# 12_CONSOLE.net
KiCad netlist of a schematic drawn in Altium Designer
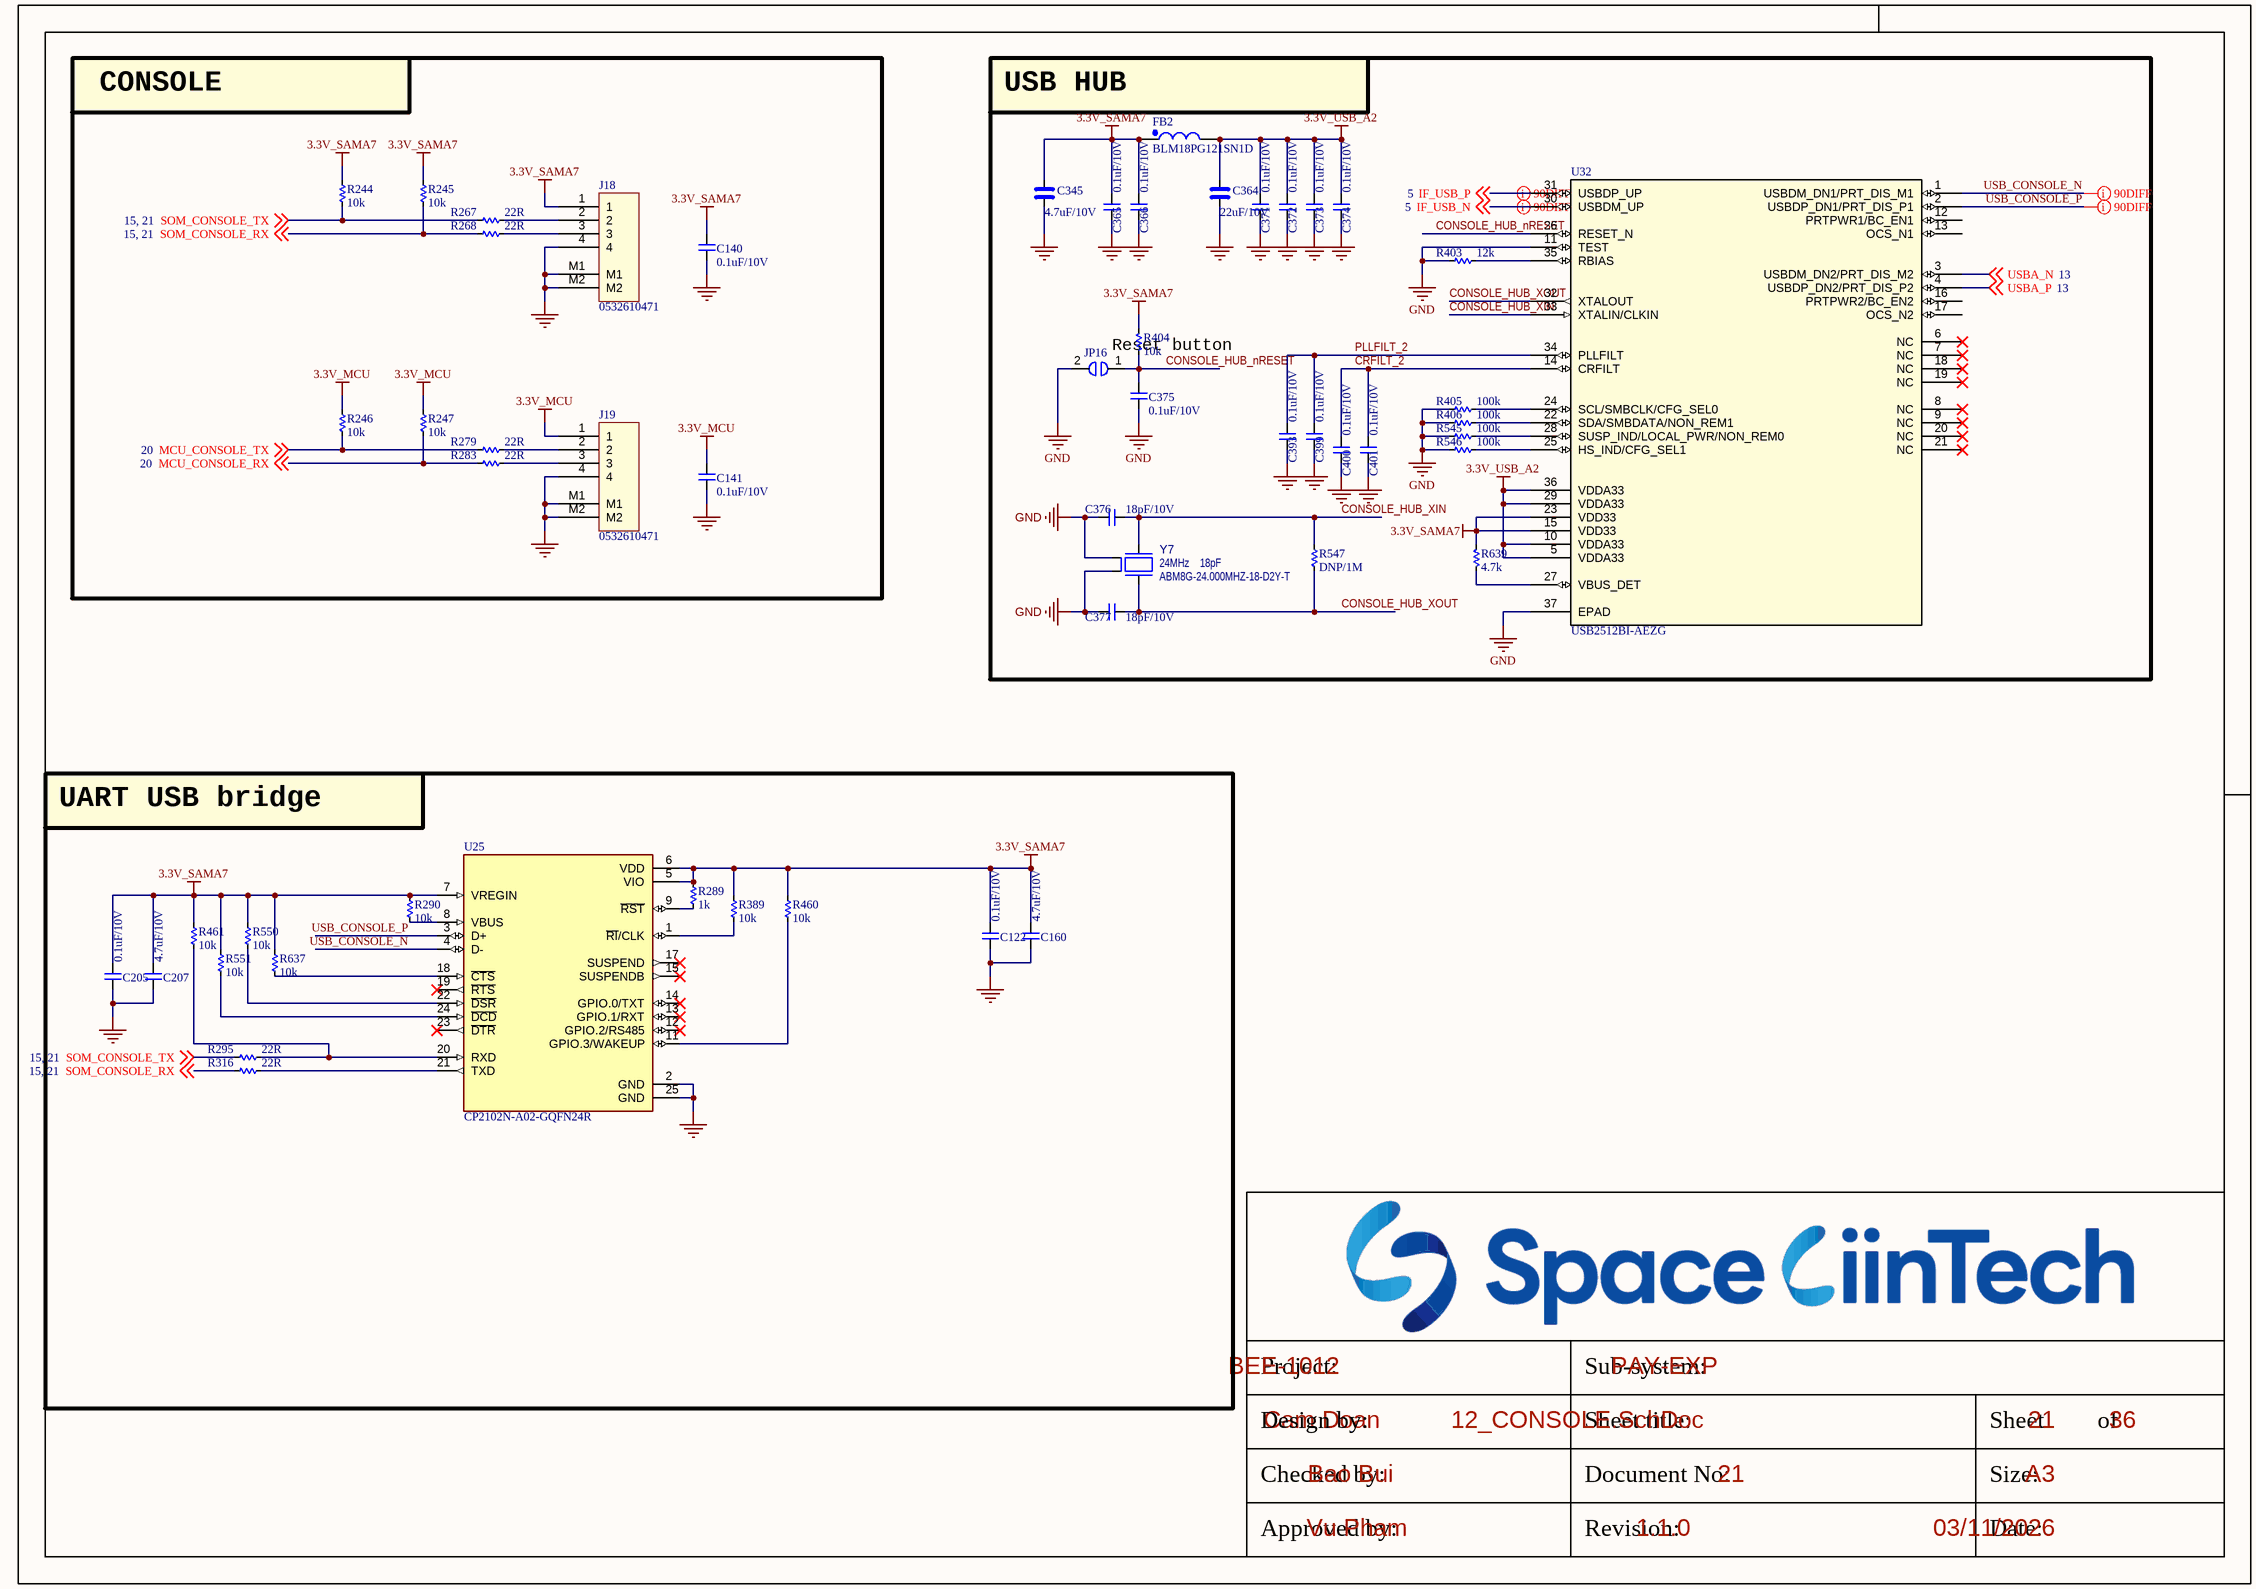
[diagram p0: 12_CONSOLE.SchDoc]

(export (version "E")
  (design (tool "Eeschema 10.0.6"))
  (components
    (comp (ref "C122")
      (value "0.1uF/10V")
      (footprint "CAP_C_1005X60")
      (description "CAP")
      (libsource (lib "LABLIB") (part "_CAP_C_2"))
    )
    (comp (ref "C140")
      (value "0.1uF/10V")
      (footprint "CAP_C_1005X60")
      (description "CAP")
      (libsource (lib "LABLIB") (part "_CAP_C_2"))
    )
    (comp (ref "C141")
      (value "0.1uF/10V")
      (footprint "CAP_C_1005X60")
      (description "CAP")
      (libsource (lib "LABLIB") (part "_CAP_C_2"))
    )
    (comp (ref "C160")
      (value "4.7uF/10V")
      (footprint "CAP_C_1005X60")
      (description "CAP")
      (libsource (lib "LABLIB") (part "_CAP_C_2"))
    )
    (comp (ref "C205")
      (value "0.1uF/10V")
      (footprint "CAP_C_1005X60")
      (description "CAP")
      (libsource (lib "LABLIB") (part "_CAP_C_2"))
    )
    (comp (ref "C207")
      (value "4.7uF/10V")
      (footprint "CAP_C_1005X60")
      (description "CAP")
      (libsource (lib "LABLIB") (part "_CAP_C_2"))
    )
    (comp (ref "C345")
      (value "4.7uF/10V")
      (footprint "CAP_C_1608X80")
      (description "CAP CHIP High Value")
      (libsource (lib "LABLIB") (part "_CAP_C_High_2"))
    )
    (comp (ref "C364")
      (value "22uF/10V")
      (footprint "CAP_C_1608X80")
      (description "CAP CHIP High Value")
      (libsource (lib "LABLIB") (part "_CAP_C_High_2"))
    )
    (comp (ref "C365")
      (value "0.1uF/10V")
      (footprint "CAP_C_1005X60")
      (description "CAP CHIP")
      (libsource (lib "LABLIB") (part "_CAP_C_2"))
    )
    (comp (ref "C366")
      (value "0.1uF/10V")
      (footprint "CAP_C_1005X60")
      (description "CAP CHIP")
      (libsource (lib "LABLIB") (part "_CAP_C_2"))
    )
    (comp (ref "C371")
      (value "0.1uF/10V")
      (footprint "CAP_C_1005X60")
      (description "CAP CHIP")
      (libsource (lib "LABLIB") (part "_CAP_C_2"))
    )
    (comp (ref "C372")
      (value "0.1uF/10V")
      (footprint "CAP_C_1005X60")
      (description "CAP CHIP")
      (libsource (lib "LABLIB") (part "_CAP_C_2"))
    )
    (comp (ref "C373")
      (value "0.1uF/10V")
      (footprint "CAP_C_1005X60")
      (description "CAP CHIP")
      (libsource (lib "LABLIB") (part "_CAP_C_2"))
    )
    (comp (ref "C374")
      (value "0.1uF/10V")
      (footprint "CAP_C_1005X60")
      (description "CAP CHIP")
      (libsource (lib "LABLIB") (part "_CAP_C_2"))
    )
    (comp (ref "C375")
      (value "0.1uF/10V")
      (footprint "CAP_C_1005X60")
      (description "CAP CHIP")
      (libsource (lib "LABLIB") (part "_CAP_C_2"))
    )
    (comp (ref "C376")
      (value "18pF/10V")
      (footprint "CAP_C_1005X60")
      (description "CAP CHIP")
      (libsource (lib "LABLIB") (part "_CAP_C_2"))
    )
    (comp (ref "C377")
      (value "18pF/10V")
      (footprint "CAP_C_1005X60")
      (description "CAP CHIP")
      (libsource (lib "LABLIB") (part "_CAP_C_2"))
    )
    (comp (ref "C393")
      (value "0.1uF/10V")
      (footprint "CAP_C_1005X60")
      (description "CAP CHIP")
      (libsource (lib "LABLIB") (part "_CAP_C_2"))
    )
    (comp (ref "C399")
      (value "0.1uF/10V")
      (footprint "CAP_C_1005X60")
      (description "CAP CHIP")
      (libsource (lib "LABLIB") (part "_CAP_C_2"))
    )
    (comp (ref "C400")
      (value "0.1uF/10V")
      (footprint "CAP_C_1005X60")
      (description "CAP CHIP")
      (libsource (lib "LABLIB") (part "_CAP_C_2"))
    )
    (comp (ref "C401")
      (value "0.1uF/10V")
      (footprint "CAP_C_1005X60")
      (description "CAP CHIP")
      (libsource (lib "LABLIB") (part "_CAP_C_2"))
    )
    (comp (ref "FB2")
      (value "BLM18PG121SN1D")
      (footprint "IND_C_1608X60")
      (libsource (lib "LABLIB") (part "_IND"))
    )
    (comp (ref "J18")
      (value "0532610471")
      (footprint "MOLEX_0532610471")
      (libsource (lib "LABLIB") (part "Header 4x1_2M"))
    )
    (comp (ref "J19")
      (value "0532610471")
      (footprint "MOLEX_0532610471")
      (libsource (lib "LABLIB") (part "Header 4x1_2M"))
    )
    (comp (ref "JP16")
      (value "~")
      (footprint "TESTPOINT_SHORT_120X100_60")
      (libsource (lib "LABLIB") (part "JUMPER_1_1"))
    )
    (comp (ref "R244")
      (value "10k")
      (footprint "RES_C_1005X40")
      (description "RES")
      (libsource (lib "LABLIB") (part "_RES_B_2"))
    )
    (comp (ref "R245")
      (value "10k")
      (footprint "RES_C_1005X40")
      (description "RES")
      (libsource (lib "LABLIB") (part "_RES_B_2"))
    )
    (comp (ref "R246")
      (value "10k")
      (footprint "RES_C_1005X40")
      (description "RES")
      (libsource (lib "LABLIB") (part "_RES_B_2"))
    )
    (comp (ref "R247")
      (value "10k")
      (footprint "RES_C_1005X40")
      (description "RES")
      (libsource (lib "LABLIB") (part "_RES_B_2"))
    )
    (comp (ref "R267")
      (value "22R")
      (footprint "RES_C_1005X40")
      (description "RES")
      (libsource (lib "LABLIB") (part "_RES_B_2"))
    )
    (comp (ref "R268")
      (value "22R")
      (footprint "RES_C_1005X40")
      (description "RES")
      (libsource (lib "LABLIB") (part "_RES_B_2"))
    )
    (comp (ref "R279")
      (value "22R")
      (footprint "RES_C_1005X40")
      (description "RES")
      (libsource (lib "LABLIB") (part "_RES_B_2"))
    )
    (comp (ref "R283")
      (value "22R")
      (footprint "RES_C_1005X40")
      (description "RES")
      (libsource (lib "LABLIB") (part "_RES_B_2"))
    )
    (comp (ref "R289")
      (value "1k")
      (footprint "RES_C_1005X40")
      (description "RES")
      (libsource (lib "LABLIB") (part "_RES_B_2"))
    )
    (comp (ref "R290")
      (value "10k")
      (footprint "RES_C_1005X40")
      (description "RES")
      (libsource (lib "LABLIB") (part "_RES_B_2"))
    )
    (comp (ref "R295")
      (value "22R")
      (footprint "RES_C_1005X40")
      (description "RES")
      (libsource (lib "LABLIB") (part "_RES_B_2"))
    )
    (comp (ref "R316")
      (value "22R")
      (footprint "RES_C_1005X40")
      (description "RES")
      (libsource (lib "LABLIB") (part "_RES_B_2"))
    )
    (comp (ref "R389")
      (value "10k")
      (footprint "RES_C_1005X40")
      (description "RES")
      (libsource (lib "LABLIB") (part "_RES_B_2"))
    )
    (comp (ref "R403")
      (value "12k")
      (footprint "RES_C_1005X40")
      (description "RES")
      (libsource (lib "LABLIB") (part "_RES_B_2"))
    )
    (comp (ref "R404")
      (value "10k")
      (footprint "RES_C_1005X40")
      (description "RES")
      (libsource (lib "LABLIB") (part "_RES_B_2"))
    )
    (comp (ref "R405")
      (value "100k")
      (footprint "RES_C_1005X40")
      (description "RES")
      (libsource (lib "LABLIB") (part "_RES_B_2"))
    )
    (comp (ref "R406")
      (value "100k")
      (footprint "RES_C_1005X40")
      (description "RES")
      (libsource (lib "LABLIB") (part "_RES_B_2"))
    )
    (comp (ref "R460")
      (value "10k")
      (footprint "RES_C_1005X40")
      (description "RES")
      (libsource (lib "LABLIB") (part "_RES_B_2"))
    )
    (comp (ref "R461")
      (value "10k")
      (footprint "RES_C_1005X40")
      (description "RES")
      (libsource (lib "LABLIB") (part "_RES_B_2"))
    )
    (comp (ref "R545")
      (value "100k")
      (footprint "RES_C_1005X40")
      (description "RES")
      (libsource (lib "LABLIB") (part "_RES_B_2"))
    )
    (comp (ref "R546")
      (value "100k")
      (footprint "RES_C_1005X40")
      (description "RES")
      (libsource (lib "LABLIB") (part "_RES_B_2"))
    )
    (comp (ref "R547")
      (value "DNP/1M")
      (footprint "RES_C_1005X40")
      (description "RES")
      (libsource (lib "LABLIB") (part "_RES_B_2"))
    )
    (comp (ref "R550")
      (value "10k")
      (footprint "RES_C_1005X40")
      (description "RES")
      (libsource (lib "LABLIB") (part "_RES_B_2"))
    )
    (comp (ref "R551")
      (value "10k")
      (footprint "RES_C_1005X40")
      (description "RES")
      (libsource (lib "LABLIB") (part "_RES_B_2"))
    )
    (comp (ref "R637")
      (value "10k")
      (footprint "RES_C_1005X40")
      (description "RES")
      (libsource (lib "LABLIB") (part "_RES_B_2"))
    )
    (comp (ref "R639")
      (value "4.7k")
      (footprint "RES_C_1005X40")
      (description "RES")
      (libsource (lib "LABLIB") (part "_RES_B_2"))
    )
    (comp (ref "U25")
      (value "CP2102N-A02-GQFN24R")
      (footprint "QFN50P400X400X80-25N")
      (libsource (lib "LABLIB") (part "IC_USB_toUART_CP2102N-A02-GQFN24R"))
    )
    (comp (ref "U32")
      (value "USB2512BI-AEZG")
      (footprint "QFN36_6X6MC_MCH")
      (description "Description")
      (fields (field (name "COPYRIGHT") "Copyright (C) 2026 Ultra Librarian. All rights reserved."))
      (libsource (lib "LABLIB") (part "IC_USB_HUB_USB2512BI-AEZG"))
    )
    (comp (ref "Y7")
      (value "24MHz")
      (footprint "CRYSTAL_ABM8G")
      (description "Crystal")
      (fields
        (field (name "LOAD CAPACITANCE") "18pF")
        (field (name "MANUFACTURER PART NUMBER 1") "ABM8G-24.000MHZ-18-D2Y-T")
        (field (name "Comment") "Crystal 4 Pins")
        (field (name "OWNER") "Mark Loper")
      )
      (libsource (lib "MCHP-CDB") (part "Crystal 4 Pins"))
    )
  )
  (nets
    (net (code "1") (name "/CONSOLE_HUB_XIN") (class "Default")
      (node (ref "C376") (pin "1") (pinfunction "1_1") (pintype "passive"))
      (node (ref "R547") (pin "1") (pinfunction "1_1") (pintype "passive"))
      (node (ref "U32") (pin "33") (pinfunction "XTALIN/CLKIN_33") (pintype "input"))
      (node (ref "Y7") (pin "3") (pinfunction "Osc2_3") (pintype "passive"))
    )
    (net (code "2") (name "/CONSOLE_HUB_XOUT") (class "Default")
      (node (ref "C377") (pin "1") (pinfunction "1_1") (pintype "passive"))
      (node (ref "R547") (pin "2") (pinfunction "2_2") (pintype "passive"))
      (node (ref "U32") (pin "32") (pinfunction "XTALOUT_32") (pintype "output"))
      (node (ref "Y7") (pin "1") (pinfunction "Osc1_1") (pintype "passive"))
    )
    (net (code "3") (name "/CONSOLE_HUB_nRESET") (class "Default")
      (node (ref "C375") (pin "2") (pinfunction "2_2") (pintype "passive"))
      (node (ref "JP16") (pin "1") (pinfunction "1_1") (pintype "passive"))
      (node (ref "R404") (pin "2") (pinfunction "2_2") (pintype "passive"))
      (node (ref "U32") (pin "26") (pinfunction "RESET_N_26") (pintype "bidirectional"))
    )
    (net (code "4") (name "/CRFILT_2") (class "Default")
      (node (ref "C400") (pin "2") (pinfunction "2_2") (pintype "passive"))
      (node (ref "C401") (pin "2") (pinfunction "2_2") (pintype "passive"))
      (node (ref "U32") (pin "14") (pinfunction "CRFILT_14") (pintype "bidirectional"))
    )
    (net (code "5") (name "/PLLFILT_2") (class "Default")
      (node (ref "C393") (pin "2") (pinfunction "2_2") (pintype "passive"))
      (node (ref "C399") (pin "2") (pinfunction "2_2") (pintype "passive"))
      (node (ref "U32") (pin "34") (pinfunction "PLLFILT_34") (pintype "bidirectional"))
    )
    (net (code "6") (name "/USB_CONSOLE_N") (class "Default")
      (node (ref "U25") (pin "4") (pinfunction "D-_4") (pintype "bidirectional"))
      (node (ref "U32") (pin "1") (pinfunction "USBDM_DN1/PRT_DIS_M1_1") (pintype "bidirectional"))
    )
    (net (code "7") (name "/USB_CONSOLE_P") (class "Default")
      (node (ref "U25") (pin "3") (pinfunction "D+_3") (pintype "bidirectional"))
      (node (ref "U32") (pin "2") (pinfunction "USBDP_DN1/PRT_DIS_P1_2") (pintype "bidirectional"))
    )
    (net (code "8") (name "3.3V_MCU") (class "Default")
      (node (ref "C141") (pin "2") (pinfunction "2_2") (pintype "passive"))
      (node (ref "J19") (pin "1") (pinfunction "1_1") (pintype "passive"))
      (node (ref "R246") (pin "2") (pinfunction "2_2") (pintype "passive"))
      (node (ref "R247") (pin "2") (pinfunction "2_2") (pintype "passive"))
    )
    (net (code "9") (name "3.3V_SAMA7") (class "Default")
      (node (ref "C122") (pin "1") (pinfunction "1_1") (pintype "passive"))
      (node (ref "C140") (pin "2") (pinfunction "2_2") (pintype "passive"))
      (node (ref "C160") (pin "1") (pinfunction "1_1") (pintype "passive"))
      (node (ref "C205") (pin "1") (pinfunction "1_1") (pintype "passive"))
      (node (ref "C207") (pin "1") (pinfunction "1_1") (pintype "passive"))
      (node (ref "C345") (pin "1") (pinfunction "1_1") (pintype "passive"))
      (node (ref "C365") (pin "2") (pinfunction "2_2") (pintype "passive"))
      (node (ref "C366") (pin "2") (pinfunction "2_2") (pintype "passive"))
      (node (ref "FB2") (pin "1") (pinfunction "1_1") (pintype "passive"))
      (node (ref "J18") (pin "1") (pinfunction "1_1") (pintype "passive"))
      (node (ref "R244") (pin "2") (pinfunction "2_2") (pintype "passive"))
      (node (ref "R245") (pin "2") (pinfunction "2_2") (pintype "passive"))
      (node (ref "R289") (pin "2") (pinfunction "2_2") (pintype "passive"))
      (node (ref "R290") (pin "2") (pinfunction "2_2") (pintype "passive"))
      (node (ref "R389") (pin "2") (pinfunction "2_2") (pintype "passive"))
      (node (ref "R404") (pin "1") (pinfunction "1_1") (pintype "passive"))
      (node (ref "R460") (pin "2") (pinfunction "2_2") (pintype "passive"))
      (node (ref "R461") (pin "2") (pinfunction "2_2") (pintype "passive"))
      (node (ref "R550") (pin "2") (pinfunction "2_2") (pintype "passive"))
      (node (ref "R551") (pin "2") (pinfunction "2_2") (pintype "passive"))
      (node (ref "R637") (pin "2") (pinfunction "2_2") (pintype "passive"))
      (node (ref "R639") (pin "1") (pinfunction "1_1") (pintype "passive"))
      (node (ref "U25") (pin "5") (pinfunction "VIO_5") (pintype "power_in"))
      (node (ref "U25") (pin "6") (pinfunction "VDD_6") (pintype "power_in"))
      (node (ref "U25") (pin "7") (pinfunction "VREGIN_7") (pintype "input"))
      (node (ref "U32") (pin "15") (pinfunction "VDD33_15") (pintype "power_in"))
      (node (ref "U32") (pin "23") (pinfunction "VDD33_23") (pintype "power_in"))
    )
    (net (code "10") (name "3.3V_USB_A2") (class "Default")
      (node (ref "C364") (pin "1") (pinfunction "1_1") (pintype "passive"))
      (node (ref "C371") (pin "2") (pinfunction "2_2") (pintype "passive"))
      (node (ref "C372") (pin "2") (pinfunction "2_2") (pintype "passive"))
      (node (ref "C373") (pin "2") (pinfunction "2_2") (pintype "passive"))
      (node (ref "C374") (pin "2") (pinfunction "2_2") (pintype "passive"))
      (node (ref "FB2") (pin "2") (pinfunction "2_2") (pintype "passive"))
      (node (ref "U32") (pin "10") (pinfunction "VDDA33_10") (pintype "power_in"))
      (node (ref "U32") (pin "29") (pinfunction "VDDA33_29") (pintype "power_in"))
      (node (ref "U32") (pin "36") (pinfunction "VDDA33_36") (pintype "power_in"))
      (node (ref "U32") (pin "5") (pinfunction "VDDA33_5") (pintype "power_in"))
    )
    (net (code "11") (name "GND") (class "Default")
      (node (ref "C122") (pin "2") (pinfunction "2_2") (pintype "passive"))
      (node (ref "C140") (pin "1") (pinfunction "1_1") (pintype "passive"))
      (node (ref "C141") (pin "1") (pinfunction "1_1") (pintype "passive"))
      (node (ref "C160") (pin "2") (pinfunction "2_2") (pintype "passive"))
      (node (ref "C205") (pin "2") (pinfunction "2_2") (pintype "passive"))
      (node (ref "C207") (pin "2") (pinfunction "2_2") (pintype "passive"))
      (node (ref "C345") (pin "2") (pinfunction "2_2") (pintype "passive"))
      (node (ref "C364") (pin "2") (pinfunction "2_2") (pintype "passive"))
      (node (ref "C365") (pin "1") (pinfunction "1_1") (pintype "passive"))
      (node (ref "C366") (pin "1") (pinfunction "1_1") (pintype "passive"))
      (node (ref "C371") (pin "1") (pinfunction "1_1") (pintype "passive"))
      (node (ref "C372") (pin "1") (pinfunction "1_1") (pintype "passive"))
      (node (ref "C373") (pin "1") (pinfunction "1_1") (pintype "passive"))
      (node (ref "C374") (pin "1") (pinfunction "1_1") (pintype "passive"))
      (node (ref "C375") (pin "1") (pinfunction "1_1") (pintype "passive"))
      (node (ref "C376") (pin "2") (pinfunction "2_2") (pintype "passive"))
      (node (ref "C377") (pin "2") (pinfunction "2_2") (pintype "passive"))
      (node (ref "C393") (pin "1") (pinfunction "1_1") (pintype "passive"))
      (node (ref "C399") (pin "1") (pinfunction "1_1") (pintype "passive"))
      (node (ref "C400") (pin "1") (pinfunction "1_1") (pintype "passive"))
      (node (ref "C401") (pin "1") (pinfunction "1_1") (pintype "passive"))
      (node (ref "J18") (pin "4") (pinfunction "4_4") (pintype "passive"))
      (node (ref "J18") (pin "M1") (pinfunction "M1_M1") (pintype "passive"))
      (node (ref "J18") (pin "M2") (pinfunction "M2_M2") (pintype "passive"))
      (node (ref "J19") (pin "4") (pinfunction "4_4") (pintype "passive"))
      (node (ref "J19") (pin "M1") (pinfunction "M1_M1") (pintype "passive"))
      (node (ref "J19") (pin "M2") (pinfunction "M2_M2") (pintype "passive"))
      (node (ref "JP16") (pin "2") (pinfunction "2_2") (pintype "passive"))
      (node (ref "R403") (pin "1") (pinfunction "1_1") (pintype "passive"))
      (node (ref "R405") (pin "1") (pinfunction "1_1") (pintype "passive"))
      (node (ref "R406") (pin "1") (pinfunction "1_1") (pintype "passive"))
      (node (ref "R545") (pin "1") (pinfunction "1_1") (pintype "passive"))
      (node (ref "R546") (pin "1") (pinfunction "1_1") (pintype "passive"))
      (node (ref "U25") (pin "2") (pinfunction "GND_2") (pintype "power_in"))
      (node (ref "U25") (pin "25") (pinfunction "GND_25") (pintype "power_in"))
      (node (ref "U32") (pin "11") (pinfunction "TEST_11") (pintype "bidirectional"))
      (node (ref "U32") (pin "37") (pinfunction "EPAD_37") (pintype "passive"))
      (node (ref "Y7") (pin "2") (pinfunction "GND_2") (pintype "power_in"))
      (node (ref "Y7") (pin "4") (pinfunction "GND_4") (pintype "power_in"))
    )
    (net (code "12") (name "IF_USB_N") (class "Default")
      (node (ref "U32") (pin "30") (pinfunction "USBDM_UP_30") (pintype "bidirectional"))
    )
    (net (code "13") (name "IF_USB_P") (class "Default")
      (node (ref "U32") (pin "31") (pinfunction "USBDP_UP_31") (pintype "bidirectional"))
    )
    (net (code "14") (name "MCU_CONSOLE_RX") (class "Default")
      (node (ref "R247") (pin "1") (pinfunction "1_1") (pintype "passive"))
      (node (ref "R283") (pin "2") (pinfunction "2_2") (pintype "passive"))
    )
    (net (code "15") (name "MCU_CONSOLE_TX") (class "Default")
      (node (ref "R246") (pin "1") (pinfunction "1_1") (pintype "passive"))
      (node (ref "R279") (pin "2") (pinfunction "2_2") (pintype "passive"))
    )
    (net (code "16") (name "Net-(J18-Pad2)") (class "Default")
      (node (ref "J18") (pin "2") (pinfunction "2_2") (pintype "passive"))
      (node (ref "R267") (pin "1") (pinfunction "1_1") (pintype "passive"))
    )
    (net (code "17") (name "Net-(J18-Pad3)") (class "Default")
      (node (ref "J18") (pin "3") (pinfunction "3_3") (pintype "passive"))
      (node (ref "R268") (pin "1") (pinfunction "1_1") (pintype "passive"))
    )
    (net (code "18") (name "Net-(J19-Pad2)") (class "Default")
      (node (ref "J19") (pin "2") (pinfunction "2_2") (pintype "passive"))
      (node (ref "R279") (pin "1") (pinfunction "1_1") (pintype "passive"))
    )
    (net (code "19") (name "Net-(J19-Pad3)") (class "Default")
      (node (ref "J19") (pin "3") (pinfunction "3_3") (pintype "passive"))
      (node (ref "R283") (pin "1") (pinfunction "1_1") (pintype "passive"))
    )
    (net (code "20") (name "Net-(U25-GPIO.3{slash}WAKEUP)") (class "Default")
      (node (ref "R460") (pin "1") (pinfunction "1_1") (pintype "passive"))
      (node (ref "U25") (pin "11") (pinfunction "GPIO.3/WAKEUP_11") (pintype "bidirectional"))
    )
    (net (code "21") (name "Net-(U25-RXD)") (class "Default")
      (node (ref "R295") (pin "1") (pinfunction "1_1") (pintype "passive"))
      (node (ref "R461") (pin "1") (pinfunction "1_1") (pintype "passive"))
      (node (ref "U25") (pin "20") (pinfunction "RXD_20") (pintype "input"))
    )
    (net (code "22") (name "Net-(U25-TXD)") (class "Default")
      (node (ref "R316") (pin "1") (pinfunction "1_1") (pintype "passive"))
      (node (ref "U25") (pin "21") (pinfunction "TXD_21") (pintype "output"))
    )
    (net (code "23") (name "Net-(U25-VBUS)") (class "Default")
      (node (ref "R290") (pin "1") (pinfunction "1_1") (pintype "passive"))
      (node (ref "U25") (pin "8") (pinfunction "VBUS_8") (pintype "input"))
    )
    (net (code "24") (name "Net-(U25-~{CTS})") (class "Default")
      (node (ref "R637") (pin "1") (pinfunction "1_1") (pintype "passive"))
      (node (ref "U25") (pin "18") (pinfunction "~{CTS}_18") (pintype "input"))
    )
    (net (code "25") (name "Net-(U25-~{DCD})") (class "Default")
      (node (ref "R551") (pin "1") (pinfunction "1_1") (pintype "passive"))
      (node (ref "U25") (pin "24") (pinfunction "~{DCD}_24") (pintype "input"))
    )
    (net (code "26") (name "Net-(U25-~{DSR})") (class "Default")
      (node (ref "R550") (pin "1") (pinfunction "1_1") (pintype "passive"))
      (node (ref "U25") (pin "22") (pinfunction "~{DSR}_22") (pintype "input"))
    )
    (net (code "27") (name "Net-(U25-~{RI}{slash}CLK)") (class "Default")
      (node (ref "R389") (pin "1") (pinfunction "1_1") (pintype "passive"))
      (node (ref "U25") (pin "1") (pinfunction "~{RI}/CLK_1") (pintype "bidirectional"))
    )
    (net (code "28") (name "Net-(U25-~{RST})") (class "Default")
      (node (ref "R289") (pin "1") (pinfunction "1_1") (pintype "passive"))
      (node (ref "U25") (pin "9") (pinfunction "~{RST}_9") (pintype "bidirectional"))
    )
    (net (code "29") (name "Net-(U32-HS_IND{slash}CFG_SEL1)") (class "Default")
      (node (ref "R546") (pin "2") (pinfunction "2_2") (pintype "passive"))
      (node (ref "U32") (pin "25") (pinfunction "HS_IND/CFG_SEL1_25") (pintype "bidirectional"))
    )
    (net (code "30") (name "Net-(U32-RBIAS)") (class "Default")
      (node (ref "R403") (pin "2") (pinfunction "2_2") (pintype "passive"))
      (node (ref "U32") (pin "35") (pinfunction "RBIAS_35") (pintype "bidirectional"))
    )
    (net (code "31") (name "Net-(U32-SCL{slash}SMBCLK{slash}CFG_SEL0)") (class "Default")
      (node (ref "R405") (pin "2") (pinfunction "2_2") (pintype "passive"))
      (node (ref "U32") (pin "24") (pinfunction "SCL/SMBCLK/CFG_SEL0_24") (pintype "bidirectional"))
    )
    (net (code "32") (name "Net-(U32-SDA{slash}SMBDATA{slash}NON_REM1)") (class "Default")
      (node (ref "R406") (pin "2") (pinfunction "2_2") (pintype "passive"))
      (node (ref "U32") (pin "22") (pinfunction "SDA/SMBDATA/NON_REM1_22") (pintype "bidirectional"))
    )
    (net (code "33") (name "Net-(U32-SUSP_IND{slash}LOCAL_PWR{slash}NON_REM0)") (class "Default")
      (node (ref "R545") (pin "2") (pinfunction "2_2") (pintype "passive"))
      (node (ref "U32") (pin "28") (pinfunction "SUSP_IND/LOCAL_PWR/NON_REM0_28") (pintype "bidirectional"))
    )
    (net (code "34") (name "Net-(U32-VBUS_DET)") (class "Default")
      (node (ref "R639") (pin "2") (pinfunction "2_2") (pintype "passive"))
      (node (ref "U32") (pin "27") (pinfunction "VBUS_DET_27") (pintype "bidirectional"))
    )
    (net (code "35") (name "SOM_CONSOLE_RX") (class "Default")
      (node (ref "R245") (pin "1") (pinfunction "1_1") (pintype "passive"))
      (node (ref "R268") (pin "2") (pinfunction "2_2") (pintype "passive"))
      (node (ref "R316") (pin "2") (pinfunction "2_2") (pintype "passive"))
    )
    (net (code "36") (name "SOM_CONSOLE_TX") (class "Default")
      (node (ref "R244") (pin "1") (pinfunction "1_1") (pintype "passive"))
      (node (ref "R267") (pin "2") (pinfunction "2_2") (pintype "passive"))
      (node (ref "R295") (pin "2") (pinfunction "2_2") (pintype "passive"))
    )
    (net (code "37") (name "USBA_N") (class "Default")
      (node (ref "U32") (pin "3") (pinfunction "USBDM_DN2/PRT_DIS_M2_3") (pintype "bidirectional"))
    )
    (net (code "38") (name "USBA_P") (class "Default")
      (node (ref "U32") (pin "4") (pinfunction "USBDP_DN2/PRT_DIS_P2_4") (pintype "bidirectional"))
    )
    (net (code "39") (name "unconnected-(U25-GPIO.0{slash}TXT-Pad14)") (class "Default")
      (node (ref "U25") (pin "14") (pinfunction "GPIO.0/TXT_14") (pintype "bidirectional+no_connect"))
    )
    (net (code "40") (name "unconnected-(U25-GPIO.1{slash}RXT-Pad13)") (class "Default")
      (node (ref "U25") (pin "13") (pinfunction "GPIO.1/RXT_13") (pintype "bidirectional+no_connect"))
    )
    (net (code "41") (name "unconnected-(U25-GPIO.2{slash}RS485-Pad12)") (class "Default")
      (node (ref "U25") (pin "12") (pinfunction "GPIO.2/RS485_12") (pintype "bidirectional+no_connect"))
    )
    (net (code "42") (name "unconnected-(U25-SUSPEND-Pad17)") (class "Default")
      (node (ref "U25") (pin "17") (pinfunction "SUSPEND_17") (pintype "output+no_connect"))
    )
    (net (code "43") (name "unconnected-(U25-SUSPENDB-Pad15)") (class "Default")
      (node (ref "U25") (pin "15") (pinfunction "SUSPENDB_15") (pintype "output+no_connect"))
    )
    (net (code "44") (name "unconnected-(U25-~{DTR}-Pad23)") (class "Default")
      (node (ref "U25") (pin "23") (pinfunction "~{DTR}_23") (pintype "output+no_connect"))
    )
    (net (code "45") (name "unconnected-(U25-~{RTS}-Pad19)") (class "Default")
      (node (ref "U25") (pin "19") (pinfunction "~{RTS}_19") (pintype "output+no_connect"))
    )
    (net (code "46") (name "unconnected-(U32-NC-Pad6)") (class "Default")
      (node (ref "U32") (pin "6") (pinfunction "NC_6") (pintype "passive+no_connect"))
    )
    (net (code "47") (name "unconnected-(U32-NC-Pad7)") (class "Default")
      (node (ref "U32") (pin "7") (pinfunction "NC_7") (pintype "passive+no_connect"))
    )
    (net (code "48") (name "unconnected-(U32-NC-Pad8)") (class "Default")
      (node (ref "U32") (pin "8") (pinfunction "NC_8") (pintype "passive+no_connect"))
    )
    (net (code "49") (name "unconnected-(U32-NC-Pad9)") (class "Default")
      (node (ref "U32") (pin "9") (pinfunction "NC_9") (pintype "passive+no_connect"))
    )
    (net (code "50") (name "unconnected-(U32-NC-Pad18)") (class "Default")
      (node (ref "U32") (pin "18") (pinfunction "NC_18") (pintype "passive+no_connect"))
    )
    (net (code "51") (name "unconnected-(U32-NC-Pad19)") (class "Default")
      (node (ref "U32") (pin "19") (pinfunction "NC_19") (pintype "passive+no_connect"))
    )
    (net (code "52") (name "unconnected-(U32-NC-Pad20)") (class "Default")
      (node (ref "U32") (pin "20") (pinfunction "NC_20") (pintype "passive+no_connect"))
    )
    (net (code "53") (name "unconnected-(U32-NC-Pad21)") (class "Default")
      (node (ref "U32") (pin "21") (pinfunction "NC_21") (pintype "passive+no_connect"))
    )
    (net (code "54") (name "unconnected-(U32-OCS_N1-Pad13)") (class "Default")
      (node (ref "U32") (pin "13") (pinfunction "OCS_N1_13") (pintype "bidirectional"))
    )
    (net (code "55") (name "unconnected-(U32-OCS_N2-Pad17)") (class "Default")
      (node (ref "U32") (pin "17") (pinfunction "OCS_N2_17") (pintype "bidirectional"))
    )
    (net (code "56") (name "unconnected-(U32-PRTPWR1{slash}BC_EN1-Pad12)") (class "Default")
      (node (ref "U32") (pin "12") (pinfunction "PRTPWR1/BC_EN1_12") (pintype "bidirectional"))
    )
    (net (code "57") (name "unconnected-(U32-PRTPWR2{slash}BC_EN2-Pad16)") (class "Default")
      (node (ref "U32") (pin "16") (pinfunction "PRTPWR2/BC_EN2_16") (pintype "bidirectional"))
    )
  )
)
